# load_switch_breakout.net
KiCad netlist of a schematic drawn in EAGLE
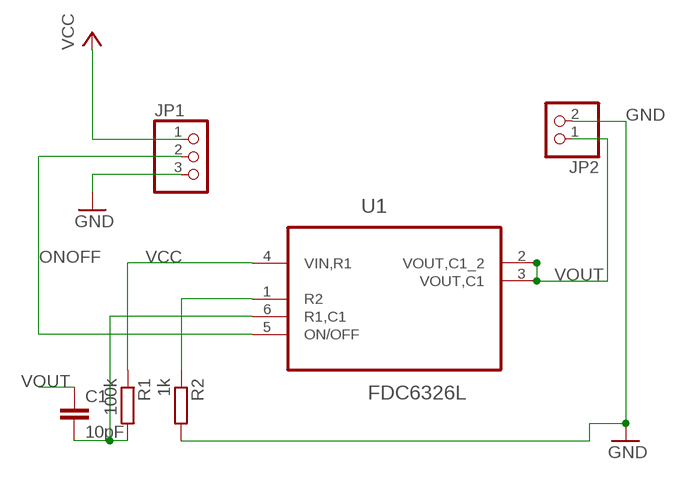
[diagram p0: schematic, sheet 1]

(export (version "E")
  (design (tool "Eeschema 10.0.6"))
  (components
    (comp (ref "C1")
      (value "10pF")
      (footprint "eagle-import:C0805K")
      (libsource (lib "eagle-import") (part "C-EUC0805K"))
    )
    (comp (ref "JP1")
      (value "PINHD-1X3")
      (footprint "eagle-import:1X03")
      (libsource (lib "eagle-import") (part "PINHD-1X3"))
    )
    (comp (ref "JP2")
      (value "PINHD-1X2")
      (footprint "eagle-import:1X02")
      (libsource (lib "eagle-import") (part "PINHD-1X2"))
    )
    (comp (ref "R1")
      (value "100k")
      (footprint "eagle-import:M0805")
      (libsource (lib "eagle-import") (part "R-EU_M0805"))
    )
    (comp (ref "R2")
      (value "1k")
      (footprint "eagle-import:M0805")
      (libsource (lib "eagle-import") (part "R-EU_M0805"))
    )
    (comp (ref "U1")
      (value "FDC6326L")
      (footprint "eagle-import:SOT95P280X110-6N")
      (libsource (lib "eagle-import") (part "FDC6326L"))
    )
  )
  (nets
    (net (code "1") (name "/ONOFF") (class "Default")
      (node (ref "JP1") (pin "2") (pinfunction "2_2") (pintype "passive"))
      (node (ref "U1") (pin "5") (pinfunction "ON/OFF_5") (pintype "input"))
    )
    (net (code "2") (name "/VOUT") (class "Default")
      (node (ref "C1") (pin "1") (pinfunction "1_1") (pintype "passive"))
      (node (ref "JP2") (pin "1") (pinfunction "1_1") (pintype "passive"))
      (node (ref "U1") (pin "2") (pinfunction "VOUT,C1_2_2") (pintype "output"))
      (node (ref "U1") (pin "3") (pinfunction "VOUT,C1_3") (pintype "output"))
    )
    (net (code "3") (name "GND") (class "Default")
      (node (ref "JP1") (pin "3") (pinfunction "3_3") (pintype "passive"))
      (node (ref "JP2") (pin "2") (pinfunction "2_2") (pintype "passive"))
      (node (ref "R2") (pin "2") (pinfunction "2_2") (pintype "passive"))
    )
    (net (code "4") (name "Net-(U1-R1,C1)") (class "Default")
      (node (ref "C1") (pin "2") (pinfunction "2_2") (pintype "passive"))
      (node (ref "R1") (pin "2") (pinfunction "2_2") (pintype "passive"))
      (node (ref "U1") (pin "6") (pinfunction "R1,C1_6") (pintype "input"))
    )
    (net (code "5") (name "Net-(U1-R2)") (class "Default")
      (node (ref "R2") (pin "1") (pinfunction "1_1") (pintype "passive"))
      (node (ref "U1") (pin "1") (pinfunction "R2_1") (pintype "input"))
    )
    (net (code "6") (name "VCC") (class "Default")
      (node (ref "JP1") (pin "1") (pinfunction "1_1") (pintype "passive"))
      (node (ref "R1") (pin "1") (pinfunction "1_1") (pintype "passive"))
      (node (ref "U1") (pin "4") (pinfunction "VIN,R1_4") (pintype "power_in"))
    )
  )
)
